# design.net
KiCad netlist of a schematic drawn in Altium Designer
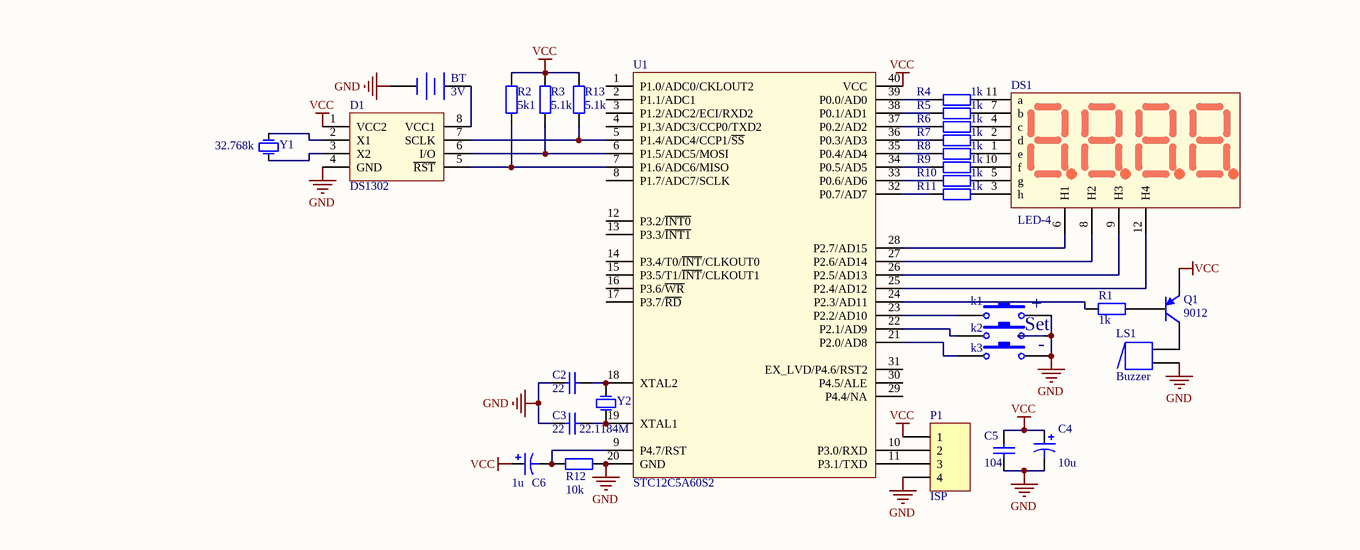
[diagram p0: 多功能数字电表.SchDoc]

(export (version "E")
  (design (tool "Eeschema 10.0.6"))
  (components
    (comp (ref "BT")
      (value "3V")
      (footprint "rb150")
      (description "Multicell Battery")
      (fields (field (name "PUBLISHER") "Altium Limited"))
      (libsource (lib "Miscellaneous Devices") (part "Battery"))
    )
    (comp (ref "C2")
      (value "22")
      (footprint "cap")
      (description "Capacitor")
      (fields (field (name "PUBLISHER") "Altium Limited"))
      (libsource (lib "Miscellaneous Devices") (part "Cap"))
    )
    (comp (ref "C3")
      (value "22")
      (footprint "cap")
      (description "Capacitor")
      (fields (field (name "PUBLISHER") "Altium Limited"))
      (libsource (lib "Miscellaneous Devices") (part "Cap"))
    )
    (comp (ref "C4")
      (value "10u")
      (footprint "RB.1/.2")
      (description "Polarized Capacitor (Radial)")
      (fields (field (name "PUBLISHER") "Altium Limited"))
      (libsource (lib "Miscellaneous Devices") (part "Cap Pol1"))
    )
    (comp (ref "C5")
      (value "104")
      (footprint "cap")
      (description "Capacitor")
      (fields (field (name "PUBLISHER") "Altium Limited"))
      (libsource (lib "Miscellaneous Devices") (part "Cap"))
    )
    (comp (ref "C6")
      (value "1u")
      (footprint "RB.1/.2")
      (description "Polarized Capacitor (Radial)")
      (fields (field (name "PUBLISHER") "Altium Limited"))
      (libsource (lib "Miscellaneous Devices") (part "Cap Pol1"))
    )
    (comp (ref "D1") (value "DS1302") (footprint "DS1302") (libsource (lib "XC173_马家俊_电子表") (part "DS1302")))
    (comp (ref "DS1")
      (value "LED-4")
      (footprint "7SEG_036*4")
      (libsource (lib "XC173_马家俊_电子表") (part "LED-4"))
    )
    (comp (ref "k1")
      (value "+")
      (footprint "SW-4")
      (description "Switch")
      (fields (field (name "PUBLISHER") "Altium Limited"))
      (libsource (lib "Miscellaneous Devices") (part "SW-PB"))
    )
    (comp (ref "k2")
      (value "Set")
      (footprint "SW-4")
      (description "Switch")
      (fields (field (name "PUBLISHER") "Altium Limited"))
      (libsource (lib "Miscellaneous Devices") (part "SW-PB"))
    )
    (comp (ref "k3")
      (value "-")
      (footprint "SW-4")
      (description "Switch")
      (fields (field (name "PUBLISHER") "Altium Limited"))
      (libsource (lib "Miscellaneous Devices") (part "SW-PB"))
    )
    (comp (ref "LS1")
      (value "Buzzer")
      (footprint "BUZZER")
      (description "Magnetic Transducer Buzzer")
      (fields (field (name "PUBLISHER") "Altium Limited"))
      (libsource (lib "XC173_马家俊_电子表_1") (part "Buzzer"))
    )
    (comp (ref "P1")
      (value "ISP")
      (footprint "sip4")
      (description "Header, 4-Pin")
      (fields (field (name "PUBLISHER") "Altium Limited"))
      (libsource (lib "Miscellaneous Connectors") (part "Header 4"))
    )
    (comp (ref "Q1")
      (value "9012")
      (footprint "to-92")
      (description "PNP General Purpose Amplifier")
      (fields (field (name "PUBLISHER") "Altium Limited"))
      (libsource (lib "Miscellaneous Devices") (part "2N3906"))
    )
    (comp (ref "R1")
      (value "1k")
      (footprint "AXIAL-0.3")
      (description "Resistor")
      (fields (field (name "PUBLISHER") "Altium Limited"))
      (libsource (lib "") (part "Res2_2"))
    )
    (comp (ref "R2")
      (value "5k1")
      (footprint "AXIAL-0.3")
      (description "Resistor")
      (fields (field (name "PUBLISHER") "Altium Limited"))
      (libsource (lib "") (part "Res2_1"))
    )
    (comp (ref "R3")
      (value "5.1k")
      (footprint "AXIAL-0.3")
      (description "Resistor")
      (fields (field (name "PUBLISHER") "Altium Limited"))
      (libsource (lib "") (part "Res2_1"))
    )
    (comp (ref "R4")
      (value "1k")
      (footprint "AXIAL-0.3")
      (description "Resistor")
      (fields (field (name "PUBLISHER") "Altium Limited"))
      (libsource (lib "Miscellaneous Devices") (part "Res2"))
    )
    (comp (ref "R5")
      (value "1k")
      (footprint "AXIAL-0.3")
      (description "Resistor")
      (fields (field (name "PUBLISHER") "Altium Limited"))
      (libsource (lib "Miscellaneous Devices") (part "Res2"))
    )
    (comp (ref "R6")
      (value "1k")
      (footprint "AXIAL-0.3")
      (description "Resistor")
      (fields (field (name "PUBLISHER") "Altium Limited"))
      (libsource (lib "Miscellaneous Devices") (part "Res2"))
    )
    (comp (ref "R7")
      (value "1k")
      (footprint "AXIAL-0.3")
      (description "Resistor")
      (fields (field (name "PUBLISHER") "Altium Limited"))
      (libsource (lib "Miscellaneous Devices") (part "Res2"))
    )
    (comp (ref "R8")
      (value "1k")
      (footprint "AXIAL-0.3")
      (description "Resistor")
      (fields (field (name "PUBLISHER") "Altium Limited"))
      (libsource (lib "Miscellaneous Devices") (part "Res2"))
    )
    (comp (ref "R9")
      (value "1k")
      (footprint "AXIAL-0.3")
      (description "Resistor")
      (fields (field (name "PUBLISHER") "Altium Limited"))
      (libsource (lib "Miscellaneous Devices") (part "Res2"))
    )
    (comp (ref "R10")
      (value "1k")
      (footprint "AXIAL-0.3")
      (description "Resistor")
      (fields (field (name "PUBLISHER") "Altium Limited"))
      (libsource (lib "Miscellaneous Devices") (part "Res2"))
    )
    (comp (ref "R11")
      (value "1k")
      (footprint "AXIAL-0.3")
      (description "Resistor")
      (fields (field (name "PUBLISHER") "Altium Limited"))
      (libsource (lib "Miscellaneous Devices") (part "Res2"))
    )
    (comp (ref "R12")
      (value "10k")
      (footprint "AXIAL-0.3")
      (description "Resistor")
      (fields (field (name "PUBLISHER") "Altium Limited"))
      (libsource (lib "Miscellaneous Devices") (part "Res2"))
    )
    (comp (ref "R13")
      (value "5.1k")
      (footprint "AXIAL-0.3")
      (description "Resistor")
      (fields (field (name "PUBLISHER") "Altium Limited"))
      (libsource (lib "") (part "Res2_1"))
    )
    (comp (ref "U1")
      (value "STC12C5A60S2")
      (footprint "DIP40")
      (libsource (lib "XC173_马家俊_电子表") (part "STC12C5A60S2"))
    )
    (comp (ref "Y1")
      (value "32.768k")
      (footprint "32768")
      (description "Crystal Oscillator")
      (fields (field (name "PUBLISHER") "Altium Limited"))
      (libsource (lib "") (part "XTAL_1"))
    )
    (comp (ref "Y2")
      (value "22.1184M")
      (footprint "XTAL")
      (description "Crystal Oscillator")
      (fields (field (name "PUBLISHER") "Altium Limited"))
      (libsource (lib "Miscellaneous Devices") (part "XTAL"))
    )
  )
  (nets
    (net (code "1") (name "GND") (class "Default")
      (node (ref "BT") (pin "2") (pinfunction "-_2") (pintype "passive"))
      (node (ref "C2") (pin "1") (pinfunction "1_1") (pintype "passive"))
      (node (ref "C3") (pin "1") (pinfunction "1_1") (pintype "passive"))
      (node (ref "C4") (pin "2") (pinfunction "2_2") (pintype "passive"))
      (node (ref "C5") (pin "1") (pinfunction "1_1") (pintype "passive"))
      (node (ref "D1") (pin "4") (pinfunction "GND_4") (pintype "passive"))
      (node (ref "LS1") (pin "2") (pinfunction "2_2") (pintype "passive"))
      (node (ref "P1") (pin "4") (pinfunction "4_4") (pintype "passive"))
      (node (ref "R12") (pin "2") (pinfunction "2_2") (pintype "passive"))
      (node (ref "U1") (pin "20") (pinfunction "GND_20") (pintype "passive"))
      (node (ref "k1") (pin "2") (pinfunction "2_2") (pintype "passive"))
      (node (ref "k2") (pin "2") (pinfunction "2_2") (pintype "passive"))
      (node (ref "k3") (pin "2") (pinfunction "2_2") (pintype "passive"))
    )
    (net (code "2") (name "Net-(BT-+)") (class "Default")
      (node (ref "BT") (pin "1") (pinfunction "+_1") (pintype "passive"))
      (node (ref "D1") (pin "8") (pinfunction "VCC1_8") (pintype "passive"))
    )
    (net (code "3") (name "Net-(D1-I{slash}O)") (class "Default")
      (node (ref "D1") (pin "6") (pinfunction "I/O_6") (pintype "passive"))
      (node (ref "R3") (pin "1") (pinfunction "1_1") (pintype "passive"))
      (node (ref "U1") (pin "6") (pinfunction "P1.5/ADC5/MOSI_6") (pintype "passive"))
    )
    (net (code "4") (name "Net-(D1-SCLK)") (class "Default")
      (node (ref "D1") (pin "7") (pinfunction "SCLK_7") (pintype "passive"))
      (node (ref "R13") (pin "1") (pinfunction "1_1") (pintype "passive"))
      (node (ref "U1") (pin "5") (pinfunction "P1.4/ADC4/CCP1/~{SS}_5") (pintype "passive"))
    )
    (net (code "5") (name "Net-(D1-X1)") (class "Default")
      (node (ref "D1") (pin "2") (pinfunction "X1_2") (pintype "passive"))
      (node (ref "Y1") (pin "2") (pinfunction "OSC2_2") (pintype "passive"))
    )
    (net (code "6") (name "Net-(D1-X2)") (class "Default")
      (node (ref "D1") (pin "3") (pinfunction "X2_3") (pintype "passive"))
      (node (ref "Y1") (pin "1") (pinfunction "OSC1_1") (pintype "passive"))
    )
    (net (code "7") (name "Net-(D1-~{RST})") (class "Default")
      (node (ref "D1") (pin "5") (pinfunction "~{RST}_5") (pintype "passive"))
      (node (ref "R2") (pin "1") (pinfunction "1_1") (pintype "passive"))
      (node (ref "U1") (pin "7") (pinfunction "P1.6/ADC6/MISO_7") (pintype "passive"))
    )
    (net (code "8") (name "Net-(DS1-H1)") (class "Default")
      (node (ref "DS1") (pin "6") (pinfunction "H1_6") (pintype "passive"))
      (node (ref "U1") (pin "28") (pinfunction "P2.7/AD15_28") (pintype "passive"))
    )
    (net (code "9") (name "Net-(DS1-H2)") (class "Default")
      (node (ref "DS1") (pin "8") (pinfunction "H2_8") (pintype "passive"))
      (node (ref "U1") (pin "27") (pinfunction "P2.6/AD14_27") (pintype "passive"))
    )
    (net (code "10") (name "Net-(DS1-H3)") (class "Default")
      (node (ref "DS1") (pin "9") (pinfunction "H3_9") (pintype "passive"))
      (node (ref "U1") (pin "26") (pinfunction "P2.5/AD13_26") (pintype "passive"))
    )
    (net (code "11") (name "Net-(DS1-H4)") (class "Default")
      (node (ref "DS1") (pin "12") (pinfunction "H4_12") (pintype "passive"))
      (node (ref "U1") (pin "25") (pinfunction "P2.4/AD12_25") (pintype "passive"))
    )
    (net (code "12") (name "Net-(DS1-a)") (class "Default")
      (node (ref "DS1") (pin "11") (pinfunction "a_11") (pintype "passive"))
      (node (ref "R4") (pin "2") (pinfunction "2_2") (pintype "passive"))
    )
    (net (code "13") (name "Net-(DS1-b)") (class "Default")
      (node (ref "DS1") (pin "7") (pinfunction "b_7") (pintype "passive"))
      (node (ref "R5") (pin "2") (pinfunction "2_2") (pintype "passive"))
    )
    (net (code "14") (name "Net-(DS1-c)") (class "Default")
      (node (ref "DS1") (pin "4") (pinfunction "c_4") (pintype "passive"))
      (node (ref "R6") (pin "2") (pinfunction "2_2") (pintype "passive"))
    )
    (net (code "15") (name "Net-(DS1-d)") (class "Default")
      (node (ref "DS1") (pin "2") (pinfunction "d_2") (pintype "passive"))
      (node (ref "R7") (pin "2") (pinfunction "2_2") (pintype "passive"))
    )
    (net (code "16") (name "Net-(DS1-e)") (class "Default")
      (node (ref "DS1") (pin "1") (pinfunction "e_1") (pintype "passive"))
      (node (ref "R8") (pin "2") (pinfunction "2_2") (pintype "passive"))
    )
    (net (code "17") (name "Net-(DS1-f)") (class "Default")
      (node (ref "DS1") (pin "10") (pinfunction "f_10") (pintype "passive"))
      (node (ref "R9") (pin "2") (pinfunction "2_2") (pintype "passive"))
    )
    (net (code "18") (name "Net-(DS1-g)") (class "Default")
      (node (ref "DS1") (pin "5") (pinfunction "g_5") (pintype "passive"))
      (node (ref "R10") (pin "2") (pinfunction "2_2") (pintype "passive"))
    )
    (net (code "19") (name "Net-(DS1-h)") (class "Default")
      (node (ref "DS1") (pin "3") (pinfunction "h_3") (pintype "passive"))
      (node (ref "R11") (pin "2") (pinfunction "2_2") (pintype "passive"))
    )
    (net (code "20") (name "Net-(Q1-B)") (class "Default")
      (node (ref "Q1") (pin "2") (pinfunction "B_2") (pintype "passive"))
      (node (ref "R1") (pin "1") (pinfunction "1_1") (pintype "passive"))
    )
    (net (code "21") (name "Net-(Q1-C)") (class "Default")
      (node (ref "LS1") (pin "1") (pinfunction "1_1") (pintype "passive"))
      (node (ref "Q1") (pin "3") (pinfunction "C_3") (pintype "passive"))
    )
    (net (code "22") (name "Net-(U1-P0.0{slash}AD0)") (class "Default")
      (node (ref "R4") (pin "1") (pinfunction "1_1") (pintype "passive"))
      (node (ref "U1") (pin "39") (pinfunction "P0.0/AD0_39") (pintype "passive"))
    )
    (net (code "23") (name "Net-(U1-P0.1{slash}AD1)") (class "Default")
      (node (ref "R5") (pin "1") (pinfunction "1_1") (pintype "passive"))
      (node (ref "U1") (pin "38") (pinfunction "P0.1/AD1_38") (pintype "passive"))
    )
    (net (code "24") (name "Net-(U1-P0.2{slash}AD2)") (class "Default")
      (node (ref "R6") (pin "1") (pinfunction "1_1") (pintype "passive"))
      (node (ref "U1") (pin "37") (pinfunction "P0.2/AD2_37") (pintype "passive"))
    )
    (net (code "25") (name "Net-(U1-P0.3{slash}AD3)") (class "Default")
      (node (ref "R7") (pin "1") (pinfunction "1_1") (pintype "passive"))
      (node (ref "U1") (pin "36") (pinfunction "P0.3/AD3_36") (pintype "passive"))
    )
    (net (code "26") (name "Net-(U1-P0.4{slash}AD4)") (class "Default")
      (node (ref "R8") (pin "1") (pinfunction "1_1") (pintype "passive"))
      (node (ref "U1") (pin "35") (pinfunction "P0.4/AD4_35") (pintype "passive"))
    )
    (net (code "27") (name "Net-(U1-P0.5{slash}AD5)") (class "Default")
      (node (ref "R9") (pin "1") (pinfunction "1_1") (pintype "passive"))
      (node (ref "U1") (pin "34") (pinfunction "P0.5/AD5_34") (pintype "passive"))
    )
    (net (code "28") (name "Net-(U1-P0.6{slash}AD6)") (class "Default")
      (node (ref "R10") (pin "1") (pinfunction "1_1") (pintype "passive"))
      (node (ref "U1") (pin "33") (pinfunction "P0.6/AD6_33") (pintype "passive"))
    )
    (net (code "29") (name "Net-(U1-P0.7{slash}AD7)") (class "Default")
      (node (ref "R11") (pin "1") (pinfunction "1_1") (pintype "passive"))
      (node (ref "U1") (pin "32") (pinfunction "P0.7/AD7_32") (pintype "passive"))
    )
    (net (code "30") (name "Net-(U1-P2.0{slash}AD8)") (class "Default")
      (node (ref "U1") (pin "21") (pinfunction "P2.0/AD8_21") (pintype "passive"))
      (node (ref "k3") (pin "1") (pinfunction "1_1") (pintype "passive"))
    )
    (net (code "31") (name "Net-(U1-P2.1{slash}AD9)") (class "Default")
      (node (ref "U1") (pin "22") (pinfunction "P2.1/AD9_22") (pintype "passive"))
      (node (ref "k2") (pin "1") (pinfunction "1_1") (pintype "passive"))
    )
    (net (code "32") (name "Net-(U1-P2.2{slash}AD10)") (class "Default")
      (node (ref "U1") (pin "23") (pinfunction "P2.2/AD10_23") (pintype "passive"))
      (node (ref "k1") (pin "1") (pinfunction "1_1") (pintype "passive"))
    )
    (net (code "33") (name "Net-(U1-P2.3{slash}AD11)") (class "Default")
      (node (ref "R1") (pin "2") (pinfunction "2_2") (pintype "passive"))
      (node (ref "U1") (pin "24") (pinfunction "P2.3/AD11_24") (pintype "passive"))
    )
    (net (code "34") (name "Net-(U1-P3.0{slash}RXD)") (class "Default")
      (node (ref "P1") (pin "2") (pinfunction "2_2") (pintype "passive"))
      (node (ref "U1") (pin "10") (pinfunction "P3.0/RXD_10") (pintype "passive"))
    )
    (net (code "35") (name "Net-(U1-P3.1{slash}TXD)") (class "Default")
      (node (ref "P1") (pin "3") (pinfunction "3_3") (pintype "passive"))
      (node (ref "U1") (pin "11") (pinfunction "P3.1/TXD_11") (pintype "passive"))
    )
    (net (code "36") (name "Net-(U1-P4.7{slash}RST)") (class "Default")
      (node (ref "C6") (pin "2") (pinfunction "2_2") (pintype "passive"))
      (node (ref "R12") (pin "1") (pinfunction "1_1") (pintype "passive"))
      (node (ref "U1") (pin "9") (pinfunction "P4.7/RST_9") (pintype "passive"))
    )
    (net (code "37") (name "Net-(U1-XTAL1)") (class "Default")
      (node (ref "C3") (pin "2") (pinfunction "2_2") (pintype "passive"))
      (node (ref "U1") (pin "19") (pinfunction "XTAL1_19") (pintype "passive"))
      (node (ref "Y2") (pin "1") (pinfunction "OSC1_1") (pintype "passive"))
    )
    (net (code "38") (name "Net-(U1-XTAL2)") (class "Default")
      (node (ref "C2") (pin "2") (pinfunction "2_2") (pintype "passive"))
      (node (ref "U1") (pin "18") (pinfunction "XTAL2_18") (pintype "passive"))
      (node (ref "Y2") (pin "2") (pinfunction "OSC2_2") (pintype "passive"))
    )
    (net (code "39") (name "VCC") (class "Default")
      (node (ref "C4") (pin "1") (pinfunction "1_1") (pintype "passive"))
      (node (ref "C5") (pin "2") (pinfunction "2_2") (pintype "passive"))
      (node (ref "C6") (pin "1") (pinfunction "1_1") (pintype "passive"))
      (node (ref "D1") (pin "1") (pinfunction "VCC2_1") (pintype "passive"))
      (node (ref "P1") (pin "1") (pinfunction "1_1") (pintype "passive"))
      (node (ref "Q1") (pin "1") (pinfunction "E_1") (pintype "passive"))
      (node (ref "R13") (pin "2") (pinfunction "2_2") (pintype "passive"))
      (node (ref "R2") (pin "2") (pinfunction "2_2") (pintype "passive"))
      (node (ref "R3") (pin "2") (pinfunction "2_2") (pintype "passive"))
      (node (ref "U1") (pin "40") (pinfunction "VCC_40") (pintype "passive"))
    )
    (net (code "40") (name "unconnected-(U1-EX_LVD{slash}P4.6{slash}RST2-Pad31)") (class "Default")
      (node (ref "U1") (pin "31") (pinfunction "EX_LVD/P4.6/RST2_31") (pintype "passive"))
    )
    (net (code "41") (name "unconnected-(U1-P1.0{slash}ADC0{slash}CKLOUT2-Pad1)") (class "Default")
      (node (ref "U1") (pin "1") (pinfunction "P1.0/ADC0/CKLOUT2_1") (pintype "passive"))
    )
    (net (code "42") (name "unconnected-(U1-P1.1{slash}ADC1-Pad2)") (class "Default")
      (node (ref "U1") (pin "2") (pinfunction "P1.1/ADC1_2") (pintype "passive"))
    )
    (net (code "43") (name "unconnected-(U1-P1.2{slash}ADC2{slash}ECI{slash}RXD2-Pad3)") (class "Default")
      (node (ref "U1") (pin "3") (pinfunction "P1.2/ADC2/ECI/RXD2_3") (pintype "passive"))
    )
    (net (code "44") (name "unconnected-(U1-P1.3{slash}ADC3{slash}CCP0{slash}TXD2-Pad4)") (class "Default")
      (node (ref "U1") (pin "4") (pinfunction "P1.3/ADC3/CCP0/TXD2_4") (pintype "passive"))
    )
    (net (code "45") (name "unconnected-(U1-P1.7{slash}ADC7{slash}SCLK-Pad8)") (class "Default")
      (node (ref "U1") (pin "8") (pinfunction "P1.7/ADC7/SCLK_8") (pintype "passive"))
    )
    (net (code "46") (name "unconnected-(U1-P3.2{slash}~{INT0}-Pad12)") (class "Default")
      (node (ref "U1") (pin "12") (pinfunction "P3.2/~{INT0}_12") (pintype "passive"))
    )
    (net (code "47") (name "unconnected-(U1-P3.3{slash}~{INT1}-Pad13)") (class "Default")
      (node (ref "U1") (pin "13") (pinfunction "P3.3/~{INT1}_13") (pintype "passive"))
    )
    (net (code "48") (name "unconnected-(U1-P3.4{slash}T0{slash}~{INT}{slash}CLKOUT0-Pad14)") (class "Default")
      (node (ref "U1") (pin "14") (pinfunction "P3.4/T0/~{INT}/CLKOUT0_14") (pintype "passive"))
    )
    (net (code "49") (name "unconnected-(U1-P3.5{slash}T1{slash}~{INT}{slash}CLKOUT1-Pad15)") (class "Default")
      (node (ref "U1") (pin "15") (pinfunction "P3.5/T1/~{INT}/CLKOUT1_15") (pintype "passive"))
    )
    (net (code "50") (name "unconnected-(U1-P3.6{slash}~{WR}-Pad16)") (class "Default")
      (node (ref "U1") (pin "16") (pinfunction "P3.6/~{WR}_16") (pintype "passive"))
    )
    (net (code "51") (name "unconnected-(U1-P3.7{slash}~{RD}-Pad17)") (class "Default")
      (node (ref "U1") (pin "17") (pinfunction "P3.7/~{RD}_17") (pintype "passive"))
    )
    (net (code "52") (name "unconnected-(U1-P4.4{slash}NA-Pad29)") (class "Default")
      (node (ref "U1") (pin "29") (pinfunction "P4.4/NA_29") (pintype "passive"))
    )
    (net (code "53") (name "unconnected-(U1-P4.5{slash}ALE-Pad30)") (class "Default")
      (node (ref "U1") (pin "30") (pinfunction "P4.5/ALE_30") (pintype "passive"))
    )
  )
)
